# SCH_d_02_e_02.net
KiCad netlist of a schematic drawn in EasyEDA
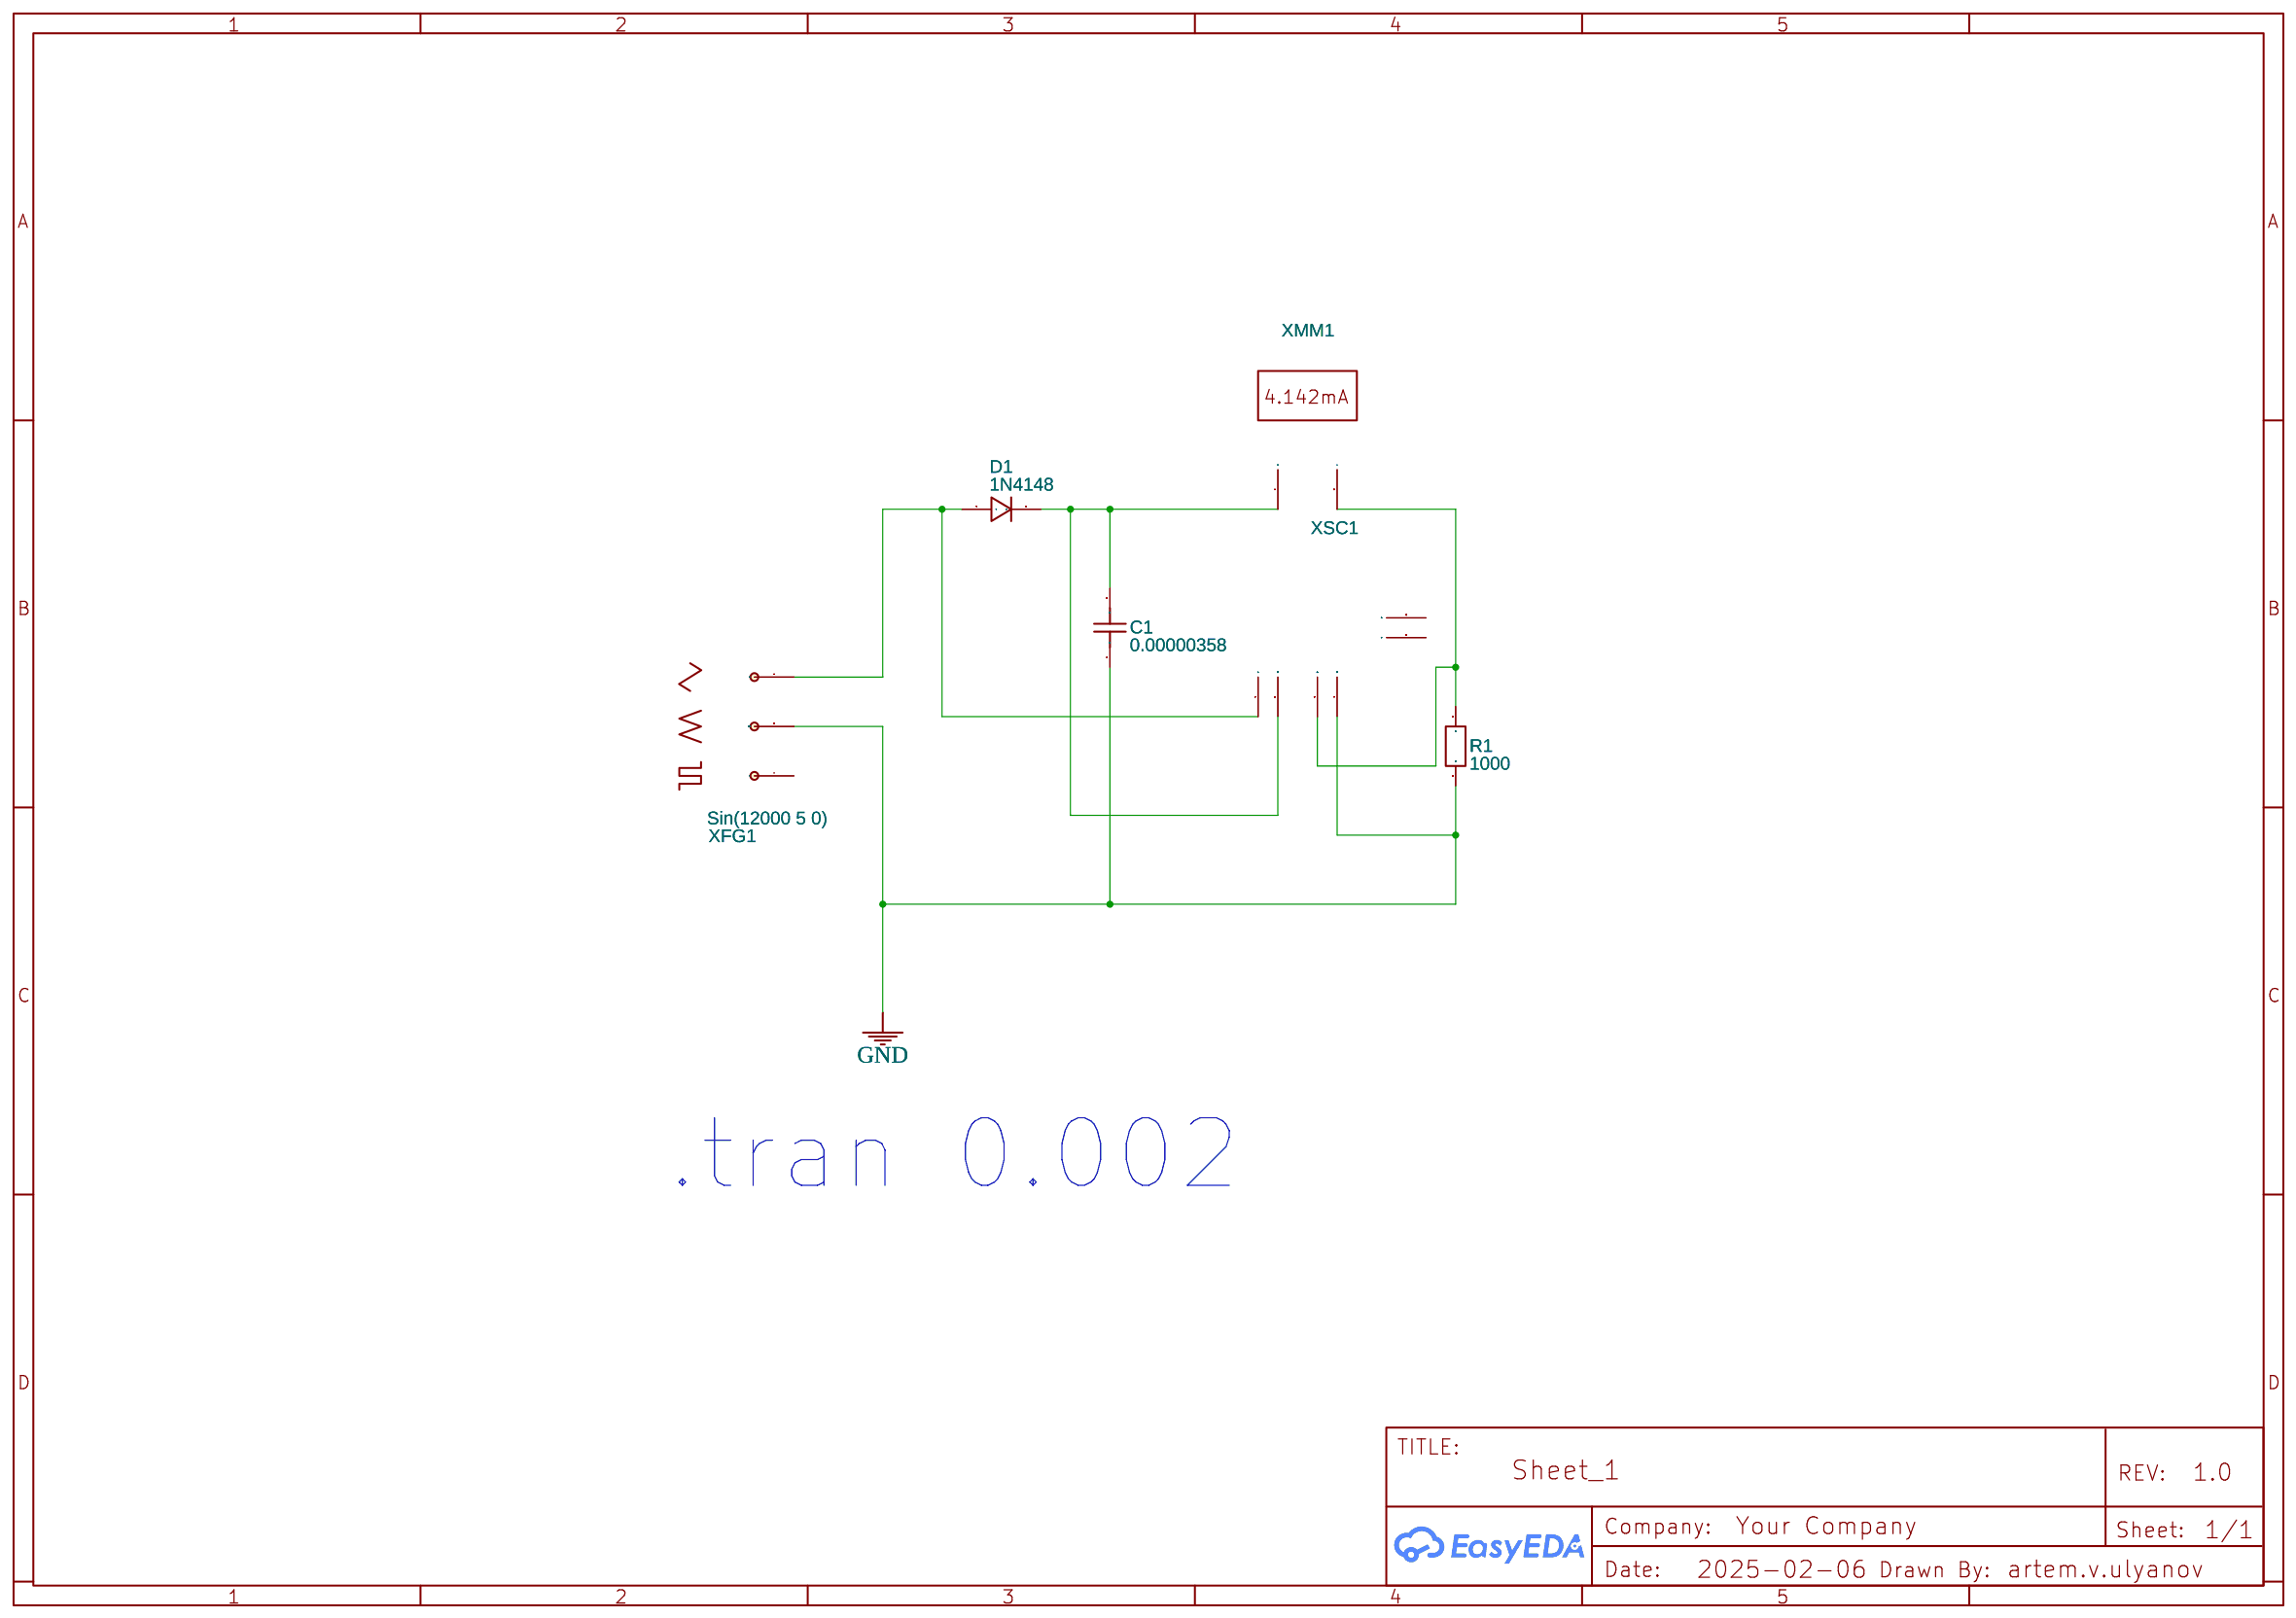
[diagram p0: schematic sheet]

(export (version "E")
  (design (tool "Eeschema 10.0.6"))
  (components
    (comp (ref "C1") (value "0.00000358") (libsource (lib "") (part "Capacitor_US")))
    (comp (ref "D1") (value "1N4148") (libsource (lib "") (part "1N4148")))
    (comp (ref "R1") (value "1000") (libsource (lib "") (part "R_0603_EU")))
    (comp (ref "XFG1") (value "Sin(12000 5 0)") (libsource (lib "") (part "FUNCTIONGENERATOR")))
    (comp (ref "XMM1") (value "Multimeter") (libsource (lib "") (part "MULTIMETER")))
    (comp (ref "XSC1") (value "Oscilloscope") (libsource (lib "") (part "OSCILLOSCOPE")))
  )
  (nets
    (net (code "1") (name "GND") (class "Default")
      (node (ref "C1") (pin "1") (pinfunction "1_1") (pintype "unspecified"))
      (node (ref "R1") (pin "2") (pinfunction "2_2") (pintype "unspecified"))
      (node (ref "XFG1") (pin "COM") (pinfunction "COM_COM") (pintype "unspecified"))
      (node (ref "XSC1") (pin "4") (pinfunction "GND2_4") (pintype "unspecified"))
    )
    (net (code "2") (name "Net-(D1-A)") (class "Default")
      (node (ref "D1") (pin "1") (pinfunction "A_1") (pintype "unspecified"))
      (node (ref "XFG1") (pin "+") (pinfunction "+_+") (pintype "unspecified"))
      (node (ref "XSC1") (pin "1") (pinfunction "A_1") (pintype "unspecified"))
    )
    (net (code "3") (name "Net-(D1-K)") (class "Default")
      (node (ref "C1") (pin "2") (pinfunction "2_2") (pintype "unspecified"))
      (node (ref "D1") (pin "2") (pinfunction "K_2") (pintype "unspecified"))
      (node (ref "XMM1") (pin "1") (pinfunction "+_1") (pintype "unspecified"))
      (node (ref "XSC1") (pin "2") (pinfunction "GND1_2") (pintype "unspecified"))
    )
    (net (code "4") (name "Net-(XMM1-I)") (class "Default")
      (node (ref "R1") (pin "1") (pinfunction "1_1") (pintype "unspecified"))
      (node (ref "XMM1") (pin "2") (pinfunction "I_2") (pintype "unspecified"))
      (node (ref "XSC1") (pin "3") (pinfunction "B_3") (pintype "unspecified"))
    )
    (net (code "5") (name "unconnected-(XFG1-Pad-)") (class "Default")
      (node (ref "XFG1") (pin "-") (pinfunction "-_-") (pintype "unspecified"))
    )
    (net (code "6") (name "unconnected-(XSC1-T+-Pad5)") (class "Default")
      (node (ref "XSC1") (pin "5") (pinfunction "T+_5") (pintype "unspecified"))
    )
    (net (code "7") (name "unconnected-(XSC1-T--Pad6)") (class "Default")
      (node (ref "XSC1") (pin "6") (pinfunction "T-_6") (pintype "unspecified"))
    )
  )
)
